# Sheet1_lab0.net
KiCad netlist of a schematic drawn in Altium Designer
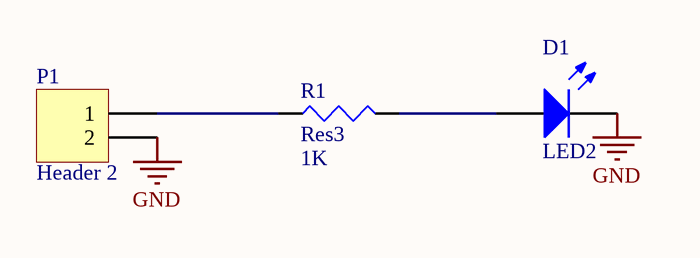
[diagram p0: Sheet1_lab0.SchDoc]

(export (version "E")
  (design (tool "Eeschema 10.0.6"))
  (components
    (comp (ref "D1")
      (value "LED2")
      (footprint "3.2X1.6X1.1")
      (description "Typical RED, GREEN, YELLOW, AMBER GaAs LED")
      (fields (field (name "PUBLISHER") "Altium Limited"))
      (libsource (lib "Miscellaneous Devices") (part "LED2"))
    )
    (comp (ref "P1")
      (value "Header 2")
      (footprint "HDR1X2")
      (description "Header, 2-Pin")
      (fields (field (name "PUBLISHER") "Altium Limited"))
      (libsource (lib "Miscellaneous Connectors") (part "Header 2"))
    )
    (comp (ref "R1")
      (value "Res3")
      (footprint "J1-0603")
      (description "Resistor")
      (fields (field (name "ALTIUM_VALUE") "1K") (field (name "PUBLISHER") "Altium Limited"))
      (libsource (lib "Miscellaneous Devices") (part "Res3"))
    )
  )
  (nets
    (net (code "1") (name "GND") (class "Default")
      (node (ref "D1") (pin "2") (pinfunction "K_2") (pintype "passive"))
      (node (ref "P1") (pin "2") (pinfunction "2_2") (pintype "passive"))
    )
    (net (code "2") (name "Net-(D1-A)") (class "Default")
      (node (ref "D1") (pin "1") (pinfunction "A_1") (pintype "passive"))
      (node (ref "R1") (pin "2") (pinfunction "2_2") (pintype "passive"))
    )
    (net (code "3") (name "Net-(P1-Pad1)") (class "Default")
      (node (ref "P1") (pin "1") (pinfunction "1_1") (pintype "passive"))
      (node (ref "R1") (pin "1") (pinfunction "1_1") (pintype "passive"))
    )
  )
)
